# Power.net
KiCad netlist of a schematic drawn in Altium Designer
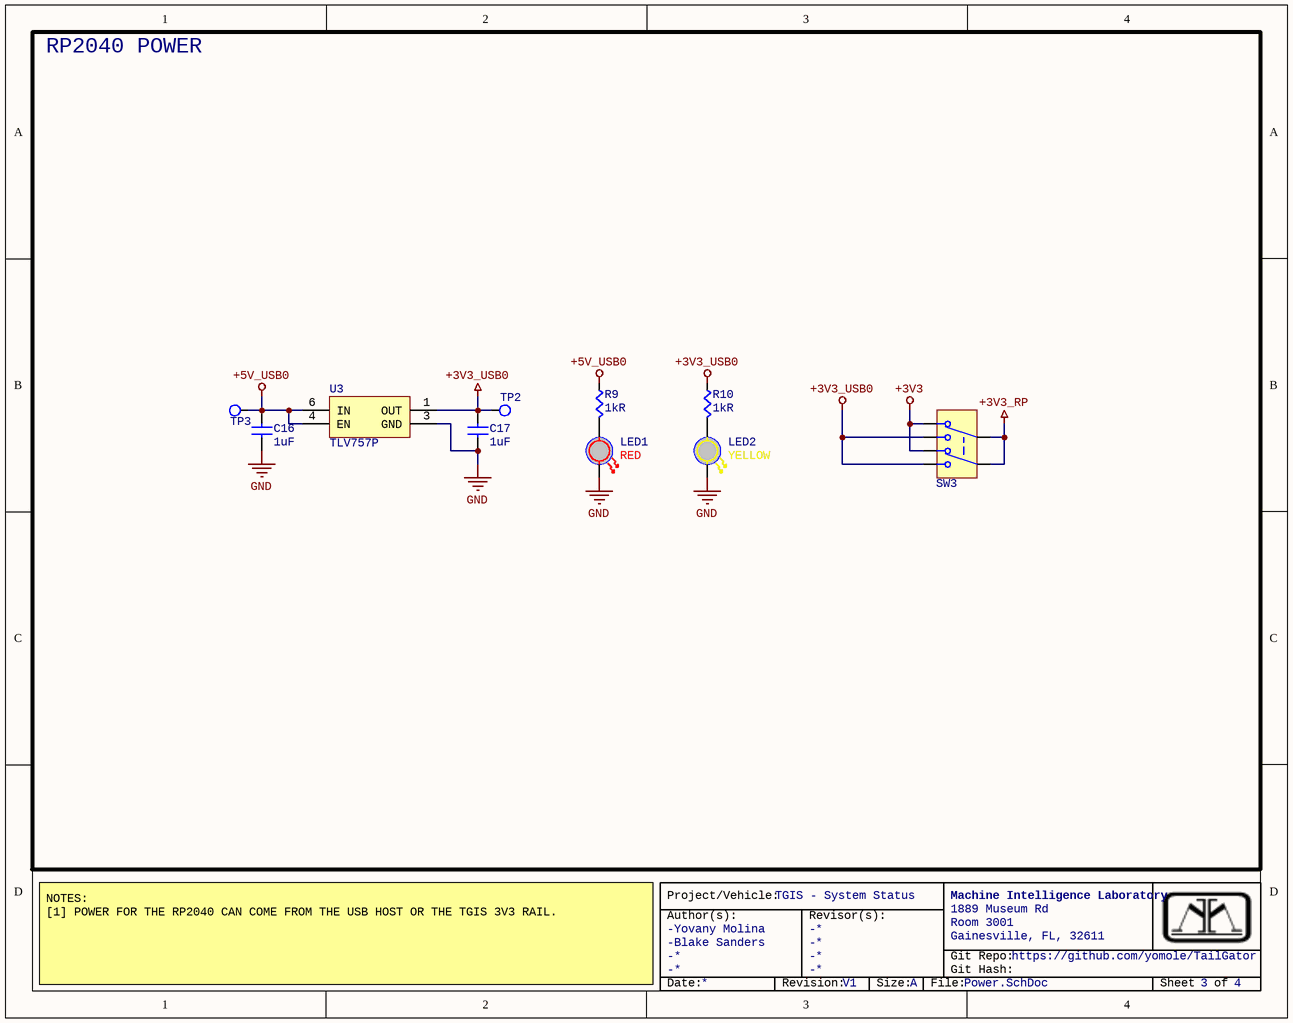
[diagram p0: Power.SchDoc]

(export (version "E")
  (design (tool "Eeschema 10.0.6"))
  (components
    (comp (ref "C16")
      (value "1uF")
      (footprint "CAPC0603")
      (description "Ceramic Capacitor, Multilayer, Cera")
      (fields (field (name "PART NUMBER") "CC0603KRX7R7BB105") (field (name "MANUFACTURER") "Yageo"))
      (libsource (lib "Parts") (part "NP_Capacitor"))
    )
    (comp (ref "C17")
      (value "1uF")
      (footprint "CAPC0603")
      (description "Ceramic Capacitor, Multilayer, Cera")
      (fields (field (name "PART NUMBER") "CC0603KRX7R7BB105") (field (name "MANUFACTURER") "Yageo"))
      (libsource (lib "Parts") (part "NP_Capacitor"))
    )
    (comp (ref "LED1")
      (value "RED")
      (footprint "LED0603")
      (description "Single Color LED, Red, Water Clear,")
      (fields (field (name "PART NUMBER") "150060RS75000") (field (name "MANUFACTURER") "Wurth Electronics"))
      (libsource (lib "Parts") (part "LED_Red"))
    )
    (comp (ref "LED2")
      (value "YELLOW")
      (footprint "LED0603")
      (description "Single Color LED, Yellow, Water Cle")
      (fields (field (name "PART NUMBER") "150060YS75000") (field (name "MANUFACTURER") "Wurth Electronics"))
      (libsource (lib "Parts") (part "LED_Yellow"))
    )
    (comp (ref "R9")
      (value "1kR")
      (footprint "RES0603")
      (description "Fixed Resistor, Metal Glaze/thick F")
      (fields (field (name "PART NUMBER") "RC0603FR-071KL") (field (name "POWER") "100mW"))
      (libsource (lib "Parts") (part "Resistor"))
    )
    (comp (ref "R10")
      (value "1kR")
      (footprint "RES0603")
      (description "Fixed Resistor, Metal Glaze/thick F")
      (fields (field (name "PART NUMBER") "RC0603FR-071KL") (field (name "POWER") "100mW"))
      (libsource (lib "Parts") (part "Resistor"))
    )
    (comp (ref "SW3")
      (value "JS202011SCQN")
      (footprint "SW_JS202011SCQN")
      (description "Slide Switch DPDT Surface Mount")
      (libsource (lib "TGIS_Power") (part "JS202011SCQN"))
    )
    (comp (ref "TP2") (value "TP") (footprint "TPAD-60MIL") (libsource (lib "TGIS") (part "TP")))
    (comp (ref "TP3") (value "TP") (footprint "TPAD-60MIL") (libsource (lib "TGIS") (part "TP")))
    (comp (ref "U3")
      (value "TLV757P")
      (footprint "VREG_TLV75733PDRVR")
      (description "Linear Voltage Regulator IC Positive Fixed 1 Output 1A 6-WSON (2x2)")
      (libsource (lib "TGIS_Power") (part "TLV75733PDRVR"))
    )
  )
  (nets
    (net (code "1") (name "+3V3") (class "Default")
      (node (ref "SW3") (pin "1") (pinfunction "1_1") (pintype "passive"))
      (node (ref "SW3") (pin "4") (pinfunction "4_4") (pintype "passive"))
    )
    (net (code "2") (name "+3V3_RP") (class "Default")
      (node (ref "SW3") (pin "2") (pinfunction "2_2") (pintype "passive"))
      (node (ref "SW3") (pin "5") (pinfunction "5_5") (pintype "passive"))
    )
    (net (code "3") (name "+3V3_USB0") (class "Default")
      (node (ref "C17") (pin "2") (pinfunction "B_2") (pintype "passive"))
      (node (ref "R10") (pin "2") (pinfunction "B_2") (pintype "passive"))
      (node (ref "SW3") (pin "3") (pinfunction "3_3") (pintype "passive"))
      (node (ref "SW3") (pin "6") (pinfunction "6_6") (pintype "passive"))
      (node (ref "TP2") (pin "1") (pinfunction "1_1") (pintype "passive"))
      (node (ref "U3") (pin "1") (pinfunction "OUT_1") (pintype "passive"))
    )
    (net (code "4") (name "+5V_USB0") (class "Default")
      (node (ref "C16") (pin "2") (pinfunction "B_2") (pintype "passive"))
      (node (ref "R9") (pin "2") (pinfunction "B_2") (pintype "passive"))
      (node (ref "TP3") (pin "1") (pinfunction "1_1") (pintype "passive"))
      (node (ref "U3") (pin "4") (pinfunction "EN_4") (pintype "passive"))
      (node (ref "U3") (pin "6") (pinfunction "IN_6") (pintype "passive"))
    )
    (net (code "5") (name "GND") (class "Default")
      (node (ref "C16") (pin "1") (pinfunction "A_1") (pintype "passive"))
      (node (ref "C17") (pin "1") (pinfunction "A_1") (pintype "passive"))
      (node (ref "LED1") (pin "C") (pinfunction "C_C") (pintype "passive"))
      (node (ref "LED2") (pin "C") (pinfunction "C_C") (pintype "passive"))
      (node (ref "U3") (pin "3") (pinfunction "GND_3") (pintype "passive"))
    )
    (net (code "6") (name "Net-(R9-A)") (class "Default")
      (node (ref "LED1") (pin "A") (pinfunction "A_A") (pintype "passive"))
      (node (ref "R9") (pin "1") (pinfunction "A_1") (pintype "passive"))
    )
    (net (code "7") (name "Net-(R10-A)") (class "Default")
      (node (ref "LED2") (pin "A") (pinfunction "A_A") (pintype "passive"))
      (node (ref "R10") (pin "1") (pinfunction "A_1") (pintype "passive"))
    )
  )
)
